# me433_krout.net
KiCad netlist of a schematic drawn in EAGLE
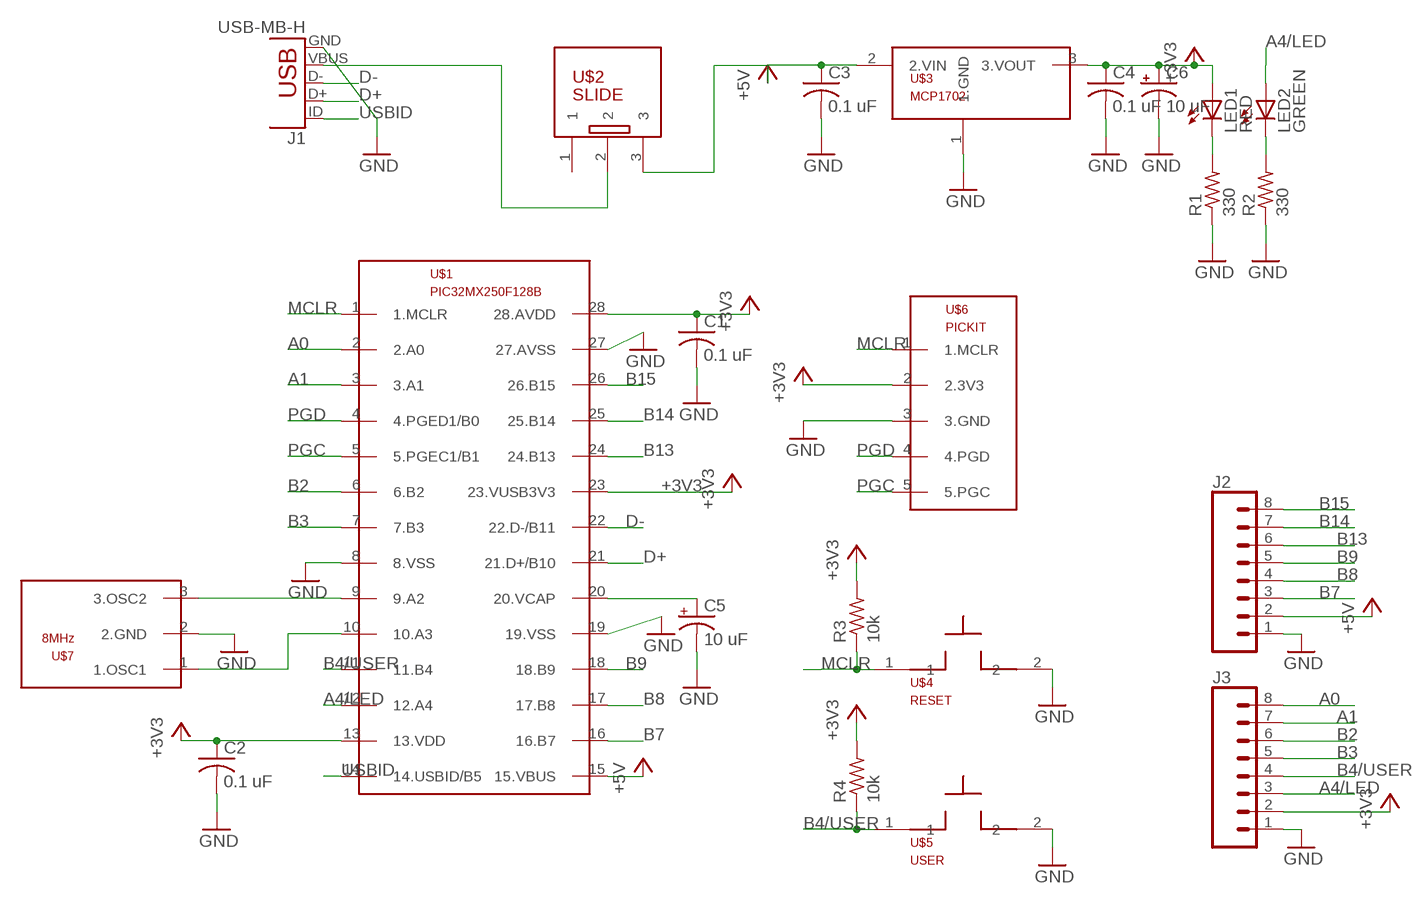
[diagram p0: schematic, sheet 1]

(export (version "E")
  (design (tool "Eeschema 10.0.6"))
  (components
    (comp (ref "C1")
      (value "0.1 uF")
      (footprint "eagle-import:C025-025X050")
      (libsource (lib "eagle-import") (part "C-US025-025X050"))
    )
    (comp (ref "C2")
      (value "0.1 uF")
      (footprint "eagle-import:C025-025X050")
      (libsource (lib "eagle-import") (part "C-US025-025X050"))
    )
    (comp (ref "C3")
      (value "0.1 uF")
      (footprint "eagle-import:C025-025X050")
      (libsource (lib "eagle-import") (part "C-US025-025X050"))
    )
    (comp (ref "C4")
      (value "0.1 uF")
      (footprint "eagle-import:C025-025X050")
      (libsource (lib "eagle-import") (part "C-US025-025X050"))
    )
    (comp (ref "C5")
      (value "10 uF")
      (footprint "eagle-import:B45181B")
      (libsource (lib "eagle-import") (part "CPOL-USB45181B"))
    )
    (comp (ref "C6")
      (value "10 uF")
      (footprint "eagle-import:B45181B")
      (libsource (lib "eagle-import") (part "CPOL-USB45181B"))
    )
    (comp (ref "J1")
      (value "USB-MB-H")
      (footprint "eagle-import:USB-MB-H")
      (libsource (lib "eagle-import") (part "USB-MB-H"))
    )
    (comp (ref "J2")
      (value "CONN_08\"")
      (footprint "eagle-import:1X08")
      (libsource (lib "eagle-import") (part "CONN_08{dblquote}"))
    )
    (comp (ref "J3")
      (value "CONN_08\"")
      (footprint "eagle-import:1X08")
      (libsource (lib "eagle-import") (part "CONN_08{dblquote}"))
    )
    (comp (ref "LED1")
      (value "RED")
      (footprint "eagle-import:LED3MM")
      (libsource (lib "eagle-import") (part "LED3MM"))
    )
    (comp (ref "LED2")
      (value "GREEN")
      (footprint "eagle-import:LED3MM")
      (libsource (lib "eagle-import") (part "LED3MM"))
    )
    (comp (ref "R1")
      (value "330")
      (footprint "eagle-import:0207_10")
      (libsource (lib "eagle-import") (part "R-US_0207/10"))
    )
    (comp (ref "R2")
      (value "330")
      (footprint "eagle-import:0207_10")
      (libsource (lib "eagle-import") (part "R-US_0207/10"))
    )
    (comp (ref "R3")
      (value "10k")
      (footprint "eagle-import:0207_10")
      (libsource (lib "eagle-import") (part "R-US_0207/10"))
    )
    (comp (ref "R4")
      (value "10k")
      (footprint "eagle-import:0207_10")
      (libsource (lib "eagle-import") (part "R-US_0207/10"))
    )
    (comp (ref "U$1")
      (value "PIC32MX250F128B")
      (footprint "eagle-import:DIL28-3")
      (libsource (lib "eagle-import") (part "PIC32MX250F128B"))
    )
    (comp (ref "U$2")
      (value "SLIDE")
      (footprint "eagle-import:SLIDE")
      (libsource (lib "eagle-import") (part "SLIDE"))
    )
    (comp (ref "U$3")
      (value "MCP1702")
      (footprint "eagle-import:TO92")
      (libsource (lib "eagle-import") (part "MCP1702"))
    )
    (comp (ref "U$4")
      (value "RESET")
      (footprint "eagle-import:PB")
      (libsource (lib "eagle-import") (part "PB"))
    )
    (comp (ref "U$5")
      (value "USER")
      (footprint "eagle-import:PB")
      (libsource (lib "eagle-import") (part "PB"))
    )
    (comp (ref "U$6")
      (value "PICKIT")
      (footprint "eagle-import:1X05")
      (libsource (lib "eagle-import") (part "PICKIT"))
    )
    (comp (ref "U$7")
      (value "8MHz")
      (footprint "eagle-import:OSC")
      (libsource (lib "eagle-import") (part "OSC"))
    )
  )
  (nets
    (net (code "1") (name "+3V3") (class "Default")
      (node (ref "C1") (pin "1") (pinfunction "1_1") (pintype "passive"))
      (node (ref "C2") (pin "1") (pinfunction "1_1") (pintype "passive"))
      (node (ref "C4") (pin "1") (pinfunction "1_1") (pintype "passive"))
      (node (ref "C6") (pin "+") (pinfunction "+_+") (pintype "passive"))
      (node (ref "J3") (pin "2") (pinfunction "2_2") (pintype "passive"))
      (node (ref "LED1") (pin "A") (pinfunction "A_A") (pintype "passive"))
      (node (ref "R3") (pin "2") (pinfunction "2_2") (pintype "passive"))
      (node (ref "R4") (pin "2") (pinfunction "2_2") (pintype "passive"))
      (node (ref "U$1") (pin "13") (pinfunction "13.VDD_13") (pintype "bidirectional"))
      (node (ref "U$1") (pin "23") (pinfunction "23.VUSB3V3_23") (pintype "bidirectional"))
      (node (ref "U$1") (pin "28") (pinfunction "28.AVDD_28") (pintype "bidirectional"))
      (node (ref "U$3") (pin "3") (pinfunction "3.VOUT_3") (pintype "bidirectional"))
      (node (ref "U$6") (pin "2") (pinfunction "2.3V3_2") (pintype "bidirectional"))
    )
    (net (code "2") (name "+5V") (class "Default")
      (node (ref "C3") (pin "1") (pinfunction "1_1") (pintype "passive"))
      (node (ref "J2") (pin "2") (pinfunction "2_2") (pintype "passive"))
      (node (ref "U$1") (pin "15") (pinfunction "15.VBUS_15") (pintype "bidirectional"))
      (node (ref "U$2") (pin "3") (pinfunction "3_3") (pintype "bidirectional"))
      (node (ref "U$3") (pin "2") (pinfunction "2.VIN_2") (pintype "bidirectional"))
    )
    (net (code "3") (name "/A0") (class "Default")
      (node (ref "J3") (pin "8") (pinfunction "8_8") (pintype "passive"))
      (node (ref "U$1") (pin "2") (pinfunction "2.A0_2") (pintype "bidirectional"))
    )
    (net (code "4") (name "/A1") (class "Default")
      (node (ref "J3") (pin "7") (pinfunction "7_7") (pintype "passive"))
      (node (ref "U$1") (pin "3") (pinfunction "3.A1_3") (pintype "bidirectional"))
    )
    (net (code "5") (name "/A4{slash}LED") (class "Default")
      (node (ref "J3") (pin "3") (pinfunction "3_3") (pintype "passive"))
      (node (ref "LED2") (pin "A") (pinfunction "A_A") (pintype "passive"))
      (node (ref "U$1") (pin "12") (pinfunction "12.A4_12") (pintype "bidirectional"))
    )
    (net (code "6") (name "/B2") (class "Default")
      (node (ref "J3") (pin "6") (pinfunction "6_6") (pintype "passive"))
      (node (ref "U$1") (pin "6") (pinfunction "6.B2_6") (pintype "bidirectional"))
    )
    (net (code "7") (name "/B3") (class "Default")
      (node (ref "J3") (pin "5") (pinfunction "5_5") (pintype "passive"))
      (node (ref "U$1") (pin "7") (pinfunction "7.B3_7") (pintype "bidirectional"))
    )
    (net (code "8") (name "/B4{slash}USER") (class "Default")
      (node (ref "J3") (pin "4") (pinfunction "4_4") (pintype "passive"))
      (node (ref "R4") (pin "1") (pinfunction "1_1") (pintype "passive"))
      (node (ref "U$1") (pin "11") (pinfunction "11.B4_11") (pintype "bidirectional"))
      (node (ref "U$5") (pin "1") (pinfunction "1_1") (pintype "bidirectional"))
    )
    (net (code "9") (name "/B7") (class "Default")
      (node (ref "J2") (pin "3") (pinfunction "3_3") (pintype "passive"))
      (node (ref "U$1") (pin "16") (pinfunction "16.B7_16") (pintype "bidirectional"))
    )
    (net (code "10") (name "/B8") (class "Default")
      (node (ref "J2") (pin "4") (pinfunction "4_4") (pintype "passive"))
      (node (ref "U$1") (pin "17") (pinfunction "17.B8_17") (pintype "bidirectional"))
    )
    (net (code "11") (name "/B9") (class "Default")
      (node (ref "J2") (pin "5") (pinfunction "5_5") (pintype "passive"))
      (node (ref "U$1") (pin "18") (pinfunction "18.B9_18") (pintype "bidirectional"))
    )
    (net (code "12") (name "/B13") (class "Default")
      (node (ref "J2") (pin "6") (pinfunction "6_6") (pintype "passive"))
      (node (ref "U$1") (pin "24") (pinfunction "24.B13_24") (pintype "bidirectional"))
    )
    (net (code "13") (name "/B14") (class "Default")
      (node (ref "J2") (pin "7") (pinfunction "7_7") (pintype "passive"))
      (node (ref "U$1") (pin "25") (pinfunction "25.B14_25") (pintype "bidirectional"))
    )
    (net (code "14") (name "/B15") (class "Default")
      (node (ref "J2") (pin "8") (pinfunction "8_8") (pintype "passive"))
      (node (ref "U$1") (pin "26") (pinfunction "26.B15_26") (pintype "bidirectional"))
    )
    (net (code "15") (name "/D+") (class "Default")
      (node (ref "J1") (pin "D+") (pinfunction "D+_D+") (pintype "bidirectional"))
      (node (ref "U$1") (pin "21") (pinfunction "21.D+/B10_21") (pintype "bidirectional"))
    )
    (net (code "16") (name "/D-") (class "Default")
      (node (ref "J1") (pin "D-") (pinfunction "D-_D-") (pintype "bidirectional"))
      (node (ref "J1") (pin "VBUS") (pinfunction "VBUS_VBUS") (pintype "bidirectional"))
      (node (ref "U$1") (pin "22") (pinfunction "22.D-/B11_22") (pintype "bidirectional"))
      (node (ref "U$2") (pin "2") (pinfunction "2_2") (pintype "bidirectional"))
    )
    (net (code "17") (name "/MCLR") (class "Default")
      (node (ref "R3") (pin "1") (pinfunction "1_1") (pintype "passive"))
      (node (ref "U$1") (pin "1") (pinfunction "1.MCLR_1") (pintype "bidirectional"))
      (node (ref "U$4") (pin "1") (pinfunction "1_1") (pintype "bidirectional"))
      (node (ref "U$6") (pin "1") (pinfunction "1.MCLR_1") (pintype "bidirectional"))
    )
    (net (code "18") (name "/PGC") (class "Default")
      (node (ref "U$1") (pin "5") (pinfunction "5.PGEC1/B1_5") (pintype "bidirectional"))
      (node (ref "U$6") (pin "5") (pinfunction "5.PGC_5") (pintype "bidirectional"))
    )
    (net (code "19") (name "/PGD") (class "Default")
      (node (ref "U$1") (pin "4") (pinfunction "4.PGED1/B0_4") (pintype "bidirectional"))
      (node (ref "U$6") (pin "4") (pinfunction "4.PGD_4") (pintype "bidirectional"))
    )
    (net (code "20") (name "/USBID") (class "Default")
      (node (ref "J1") (pin "ID") (pinfunction "ID_ID") (pintype "bidirectional"))
      (node (ref "U$1") (pin "14") (pinfunction "14.USBID/B5_14") (pintype "bidirectional"))
    )
    (net (code "21") (name "GND") (class "Default")
      (node (ref "C1") (pin "2") (pinfunction "2_2") (pintype "passive"))
      (node (ref "C2") (pin "2") (pinfunction "2_2") (pintype "passive"))
      (node (ref "C3") (pin "2") (pinfunction "2_2") (pintype "passive"))
      (node (ref "C4") (pin "2") (pinfunction "2_2") (pintype "passive"))
      (node (ref "C5") (pin "-") (pinfunction "-_-") (pintype "passive"))
      (node (ref "C6") (pin "-") (pinfunction "-_-") (pintype "passive"))
      (node (ref "J1") (pin "GND") (pinfunction "GND_GND") (pintype "bidirectional"))
      (node (ref "J2") (pin "1") (pinfunction "1_1") (pintype "passive"))
      (node (ref "J3") (pin "1") (pinfunction "1_1") (pintype "passive"))
      (node (ref "R1") (pin "1") (pinfunction "1_1") (pintype "passive"))
      (node (ref "R2") (pin "1") (pinfunction "1_1") (pintype "passive"))
      (node (ref "U$1") (pin "19") (pinfunction "19.VSS_19") (pintype "bidirectional"))
      (node (ref "U$1") (pin "27") (pinfunction "27.AVSS_27") (pintype "bidirectional"))
      (node (ref "U$1") (pin "8") (pinfunction "8.VSS_8") (pintype "bidirectional"))
      (node (ref "U$3") (pin "1") (pinfunction "1.GND_1") (pintype "bidirectional"))
      (node (ref "U$4") (pin "2") (pinfunction "2_2") (pintype "bidirectional"))
      (node (ref "U$5") (pin "2") (pinfunction "2_2") (pintype "bidirectional"))
      (node (ref "U$6") (pin "3") (pinfunction "3.GND_3") (pintype "bidirectional"))
      (node (ref "U$7") (pin "2") (pinfunction "2.GND_2") (pintype "bidirectional"))
    )
    (net (code "22") (name "Net-(LED1-C)") (class "Default")
      (node (ref "LED1") (pin "K") (pinfunction "C_K") (pintype "passive"))
      (node (ref "R1") (pin "2") (pinfunction "2_2") (pintype "passive"))
    )
    (net (code "23") (name "Net-(LED2-C)") (class "Default")
      (node (ref "LED2") (pin "K") (pinfunction "C_K") (pintype "passive"))
      (node (ref "R2") (pin "2") (pinfunction "2_2") (pintype "passive"))
    )
    (net (code "24") (name "Net-(U$1-9.A2)") (class "Default")
      (node (ref "U$1") (pin "9") (pinfunction "9.A2_9") (pintype "bidirectional"))
      (node (ref "U$7") (pin "3") (pinfunction "3.OSC2_3") (pintype "bidirectional"))
    )
    (net (code "25") (name "Net-(U$1-10.A3)") (class "Default")
      (node (ref "U$1") (pin "10") (pinfunction "10.A3_10") (pintype "bidirectional"))
      (node (ref "U$7") (pin "1") (pinfunction "1.OSC1_1") (pintype "bidirectional"))
    )
    (net (code "26") (name "Net-(U$1-20.VCAP)") (class "Default")
      (node (ref "C5") (pin "+") (pinfunction "+_+") (pintype "passive"))
      (node (ref "U$1") (pin "20") (pinfunction "20.VCAP_20") (pintype "bidirectional"))
    )
    (net (code "27") (name "unconnected-(U$2-Pad1)") (class "Default")
      (node (ref "U$2") (pin "1") (pinfunction "1_1") (pintype "bidirectional"))
    )
  )
)
